# Brainstorm.net
KiCad netlist of a schematic drawn in EAGLE
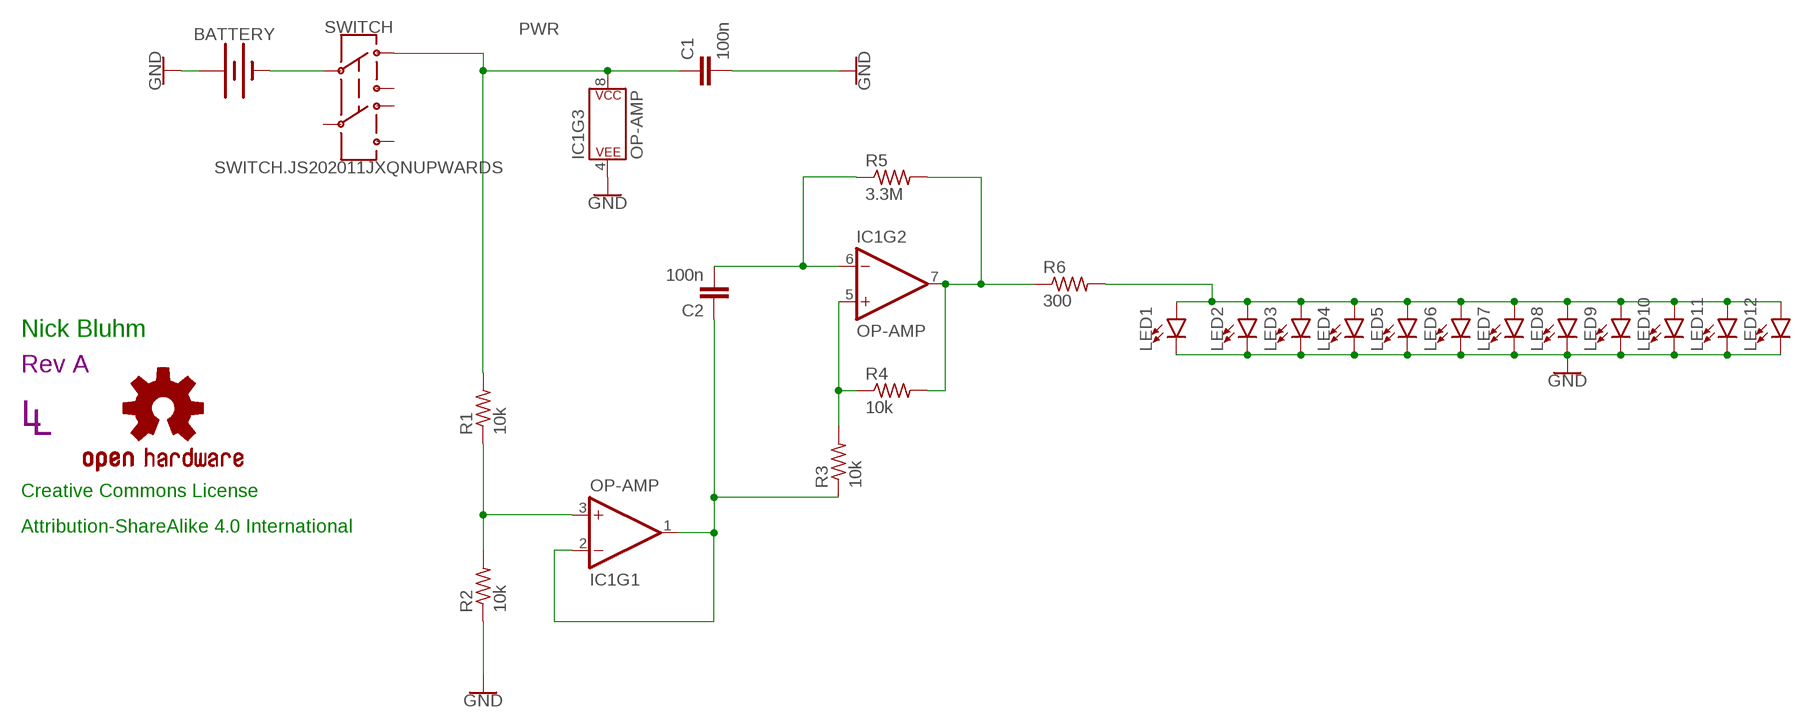
[diagram p0: schematic, sheet 1]

(export (version "E")
  (design (tool "Eeschema 10.0.6"))
  (components
    (comp (ref "BATTERY")
      (value "BATTERY-20MM_SMD")
      (footprint "eagle-import:BATTCON_20MM")
      (libsource (lib "eagle-import") (part "BATTERY-20MM_SMD"))
    )
    (comp (ref "C1")
      (value "100n")
      (footprint "eagle-import:C0402")
      (libsource (lib "eagle-import") (part "CAPACITOR0402"))
    )
    (comp (ref "C2")
      (value "100n")
      (footprint "eagle-import:C0402")
      (libsource (lib "eagle-import") (part "CAPACITOR0402"))
    )
    (comp (ref "IC1")
      (value "OP-AMP")
      (footprint "eagle-import:SO08")
      (libsource (lib "eagle-import") (part "OPAMP-DUALU"))
    )
    (comp (ref "LED1")
      (value "LED5MM")
      (footprint "eagle-import:LED_5MM")
      (libsource (lib "eagle-import") (part "LED5MM"))
    )
    (comp (ref "LED2")
      (value "LED5MM")
      (footprint "eagle-import:LED_5MM")
      (libsource (lib "eagle-import") (part "LED5MM"))
    )
    (comp (ref "LED3")
      (value "LED5MM")
      (footprint "eagle-import:LED_5MM")
      (libsource (lib "eagle-import") (part "LED5MM"))
    )
    (comp (ref "LED4")
      (value "LED5MM")
      (footprint "eagle-import:LED_5MM")
      (libsource (lib "eagle-import") (part "LED5MM"))
    )
    (comp (ref "LED5")
      (value "LED5MM")
      (footprint "eagle-import:LED_5MM")
      (libsource (lib "eagle-import") (part "LED5MM"))
    )
    (comp (ref "LED6")
      (value "LED5MM")
      (footprint "eagle-import:LED_5MM")
      (libsource (lib "eagle-import") (part "LED5MM"))
    )
    (comp (ref "LED7")
      (value "LED5MM")
      (footprint "eagle-import:LED_5MM")
      (libsource (lib "eagle-import") (part "LED5MM"))
    )
    (comp (ref "LED8")
      (value "LED5MM")
      (footprint "eagle-import:LED_5MM")
      (libsource (lib "eagle-import") (part "LED5MM"))
    )
    (comp (ref "LED9")
      (value "LED5MM")
      (footprint "eagle-import:LED_5MM")
      (libsource (lib "eagle-import") (part "LED5MM"))
    )
    (comp (ref "LED10")
      (value "LED5MM")
      (footprint "eagle-import:LED_5MM")
      (libsource (lib "eagle-import") (part "LED5MM"))
    )
    (comp (ref "LED11")
      (value "LED5MM")
      (footprint "eagle-import:LED_5MM")
      (libsource (lib "eagle-import") (part "LED5MM"))
    )
    (comp (ref "LED12")
      (value "LED5MM")
      (footprint "eagle-import:LED_5MM")
      (libsource (lib "eagle-import") (part "LED5MM"))
    )
    (comp (ref "LOGO1")
      (value "OSHW-LOGOL-COPPER")
      (footprint "eagle-import:OSHW-LOGO-L_COPPER")
      (libsource (lib "eagle-import") (part "OSHW-LOGOL-COPPER"))
    )
    (comp (ref "R1")
      (value "10k")
      (footprint "eagle-import:R0603")
      (libsource (lib "eagle-import") (part "RESISTOR0603"))
    )
    (comp (ref "R2")
      (value "10k")
      (footprint "eagle-import:R0603")
      (libsource (lib "eagle-import") (part "RESISTOR0603"))
    )
    (comp (ref "R3")
      (value "10k")
      (footprint "eagle-import:R0603")
      (libsource (lib "eagle-import") (part "RESISTOR0603"))
    )
    (comp (ref "R4")
      (value "10k")
      (footprint "eagle-import:R0603")
      (libsource (lib "eagle-import") (part "RESISTOR0603"))
    )
    (comp (ref "R5")
      (value "3.3M")
      (footprint "eagle-import:R0603")
      (libsource (lib "eagle-import") (part "RESISTOR0603"))
    )
    (comp (ref "R6")
      (value "300")
      (footprint "eagle-import:R0603")
      (libsource (lib "eagle-import") (part "RESISTOR0603"))
    )
    (comp (ref "SWITCH")
      (value "SWITCH.JS202011JXQNUPWARDS")
      (footprint "eagle-import:SWITCH.00")
      (libsource (lib "eagle-import") (part "SWITCH.JS202011JXQNUPWARDS"))
    )
    (comp (ref "U$4")
      (value "REVISION.A")
      (footprint "eagle-import:REV.A")
      (libsource (lib "eagle-import") (part "REVISION.A"))
    )
    (comp (ref "U$5")
      (value "LINNES.LAB.LOGO")
      (footprint "eagle-import:LINNES.LAB.LOGO")
      (libsource (lib "eagle-import") (part "LINNES.LAB.LOGO"))
    )
  )
  (nets
    (net (code "1") (name "/PWR") (class "Default")
      (node (ref "C1") (pin "1") (pinfunction "1_1") (pintype "passive"))
      (node (ref "IC1") (pin "8") (pinfunction "P$V+_8") (pintype "bidirectional"))
      (node (ref "R1") (pin "2") (pinfunction "2_2") (pintype "passive"))
      (node (ref "SWITCH") (pin "1") (pinfunction "1_1") (pintype "bidirectional"))
    )
    (net (code "2") (name "GND") (class "Default")
      (node (ref "BATTERY") (pin "1") (pinfunction "+_1") (pintype "power_in"))
      (node (ref "C1") (pin "2") (pinfunction "2_2") (pintype "passive"))
      (node (ref "IC1") (pin "4") (pinfunction "P$V-_4") (pintype "bidirectional"))
      (node (ref "LED1") (pin "K") (pinfunction "C_K") (pintype "passive"))
      (node (ref "LED10") (pin "K") (pinfunction "C_K") (pintype "passive"))
      (node (ref "LED11") (pin "K") (pinfunction "C_K") (pintype "passive"))
      (node (ref "LED12") (pin "K") (pinfunction "C_K") (pintype "passive"))
      (node (ref "LED2") (pin "K") (pinfunction "C_K") (pintype "passive"))
      (node (ref "LED3") (pin "K") (pinfunction "C_K") (pintype "passive"))
      (node (ref "LED4") (pin "K") (pinfunction "C_K") (pintype "passive"))
      (node (ref "LED5") (pin "K") (pinfunction "C_K") (pintype "passive"))
      (node (ref "LED6") (pin "K") (pinfunction "C_K") (pintype "passive"))
      (node (ref "LED7") (pin "K") (pinfunction "C_K") (pintype "passive"))
      (node (ref "LED8") (pin "K") (pinfunction "C_K") (pintype "passive"))
      (node (ref "LED9") (pin "K") (pinfunction "C_K") (pintype "passive"))
      (node (ref "R2") (pin "1") (pinfunction "1_1") (pintype "passive"))
    )
    (net (code "3") (name "Net-(BATTERY--)") (class "Default")
      (node (ref "BATTERY") (pin "2") (pinfunction "-_2") (pintype "power_in"))
      (node (ref "SWITCH") (pin "2") (pinfunction "2_2") (pintype "bidirectional"))
    )
    (net (code "4") (name "Net-(IC1A-+IN)") (class "Default")
      (node (ref "IC1") (pin "3") (pinfunction "+IN_3") (pintype "input"))
      (node (ref "R1") (pin "1") (pinfunction "1_1") (pintype "passive"))
      (node (ref "R2") (pin "2") (pinfunction "2_2") (pintype "passive"))
    )
    (net (code "5") (name "Net-(IC1A--IN)") (class "Default")
      (node (ref "C2") (pin "1") (pinfunction "1_1") (pintype "passive"))
      (node (ref "IC1") (pin "1") (pinfunction "OUT_1") (pintype "output"))
      (node (ref "IC1") (pin "2") (pinfunction "-IN_2") (pintype "input"))
      (node (ref "R3") (pin "1") (pinfunction "1_1") (pintype "passive"))
    )
    (net (code "6") (name "Net-(IC1B-+IN)") (class "Default")
      (node (ref "IC1") (pin "5") (pinfunction "+IN_5") (pintype "input"))
      (node (ref "R3") (pin "2") (pinfunction "2_2") (pintype "passive"))
      (node (ref "R4") (pin "1") (pinfunction "1_1") (pintype "passive"))
    )
    (net (code "7") (name "Net-(IC1B--IN)") (class "Default")
      (node (ref "C2") (pin "2") (pinfunction "2_2") (pintype "passive"))
      (node (ref "IC1") (pin "6") (pinfunction "-IN_6") (pintype "input"))
      (node (ref "R5") (pin "1") (pinfunction "1_1") (pintype "passive"))
    )
    (net (code "8") (name "Net-(IC1B-OUT)") (class "Default")
      (node (ref "IC1") (pin "7") (pinfunction "OUT_7") (pintype "output"))
      (node (ref "R4") (pin "2") (pinfunction "2_2") (pintype "passive"))
      (node (ref "R5") (pin "2") (pinfunction "2_2") (pintype "passive"))
      (node (ref "R6") (pin "1") (pinfunction "1_1") (pintype "passive"))
    )
    (net (code "9") (name "Net-(LED1-PadA)") (class "Default")
      (node (ref "LED1") (pin "A") (pinfunction "A_A") (pintype "passive"))
      (node (ref "LED10") (pin "A") (pinfunction "A_A") (pintype "passive"))
      (node (ref "LED11") (pin "A") (pinfunction "A_A") (pintype "passive"))
      (node (ref "LED12") (pin "A") (pinfunction "A_A") (pintype "passive"))
      (node (ref "LED2") (pin "A") (pinfunction "A_A") (pintype "passive"))
      (node (ref "LED3") (pin "A") (pinfunction "A_A") (pintype "passive"))
      (node (ref "LED4") (pin "A") (pinfunction "A_A") (pintype "passive"))
      (node (ref "LED5") (pin "A") (pinfunction "A_A") (pintype "passive"))
      (node (ref "LED6") (pin "A") (pinfunction "A_A") (pintype "passive"))
      (node (ref "LED7") (pin "A") (pinfunction "A_A") (pintype "passive"))
      (node (ref "LED8") (pin "A") (pinfunction "A_A") (pintype "passive"))
      (node (ref "LED9") (pin "A") (pinfunction "A_A") (pintype "passive"))
      (node (ref "R6") (pin "2") (pinfunction "2_2") (pintype "passive"))
    )
    (net (code "10") (name "unconnected-(SWITCH-Pad3)") (class "Default")
      (node (ref "SWITCH") (pin "3") (pinfunction "3_3") (pintype "bidirectional"))
    )
    (net (code "11") (name "unconnected-(SWITCH-Pad5)") (class "Default")
      (node (ref "SWITCH") (pin "5") (pinfunction "5_5") (pintype "bidirectional"))
    )
    (net (code "12") (name "unconnected-(SWITCH-Pad6)") (class "Default")
      (node (ref "SWITCH") (pin "6") (pinfunction "6_6") (pintype "bidirectional"))
    )
    (net (code "13") (name "unconnected-(SWITCH-Pad7)") (class "Default")
      (node (ref "SWITCH") (pin "7") (pinfunction "7_7") (pintype "bidirectional"))
    )
  )
)
